# LCD.net
KiCad netlist of a schematic drawn in Altium Designer
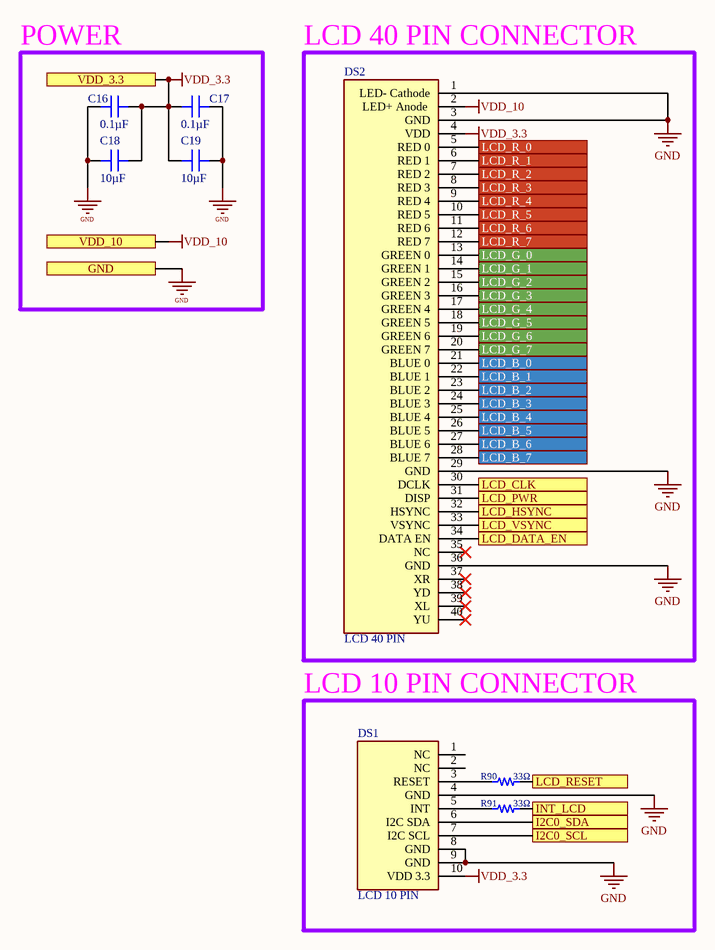
[diagram p0: LCD.SchDoc]

(export (version "E")
  (design (tool "Eeschema 10.0.6"))
  (components
    (comp (ref "C16")
      (value "0.1µF")
      (footprint "CAP 0603_1608 RF")
      (description "CAP CER 0.1UF 16V X7R 0603")
      (fields (field (name "MANUFACTURER") "KEMET") (field (name "VOLTAGE") "16V"))
      (libsource (lib "MVVVMAltiumDatabase") (part "Capacitor"))
    )
    (comp (ref "C17")
      (value "0.1µF")
      (footprint "CAP 0603_1608 RF")
      (description "CAP CER 0.1UF 16V X7R 0603")
      (fields (field (name "MANUFACTURER") "KEMET") (field (name "VOLTAGE") "16V"))
      (libsource (lib "MVVVMAltiumDatabase") (part "Capacitor"))
    )
    (comp (ref "C18")
      (value "10µF")
      (footprint "CAP 0603_1608")
      (description "CAP CER 010UF 25V X7R 0603")
      (fields (field (name "MANUFACTURER") "KEMET") (field (name "VOLTAGE") "25V"))
      (libsource (lib "MVVVMAltiumDatabase") (part "Capacitor"))
    )
    (comp (ref "C19")
      (value "10µF")
      (footprint "CAP 0603_1608")
      (description "CAP CER 010UF 25V X7R 0603")
      (fields (field (name "MANUFACTURER") "KEMET") (field (name "VOLTAGE") "25V"))
      (libsource (lib "MVVVMAltiumDatabase") (part "Capacitor"))
    )
    (comp (ref "DS1")
      (value "LCD 10 PIN")
      (footprint "4DLCD-70800480-CTP-CLB 10 PIN")
      (description "LED GRN/RED CLEAR 4SMD BOTTOM")
      (fields (field (name "MANUFACTURER") "Würth Elektronik"))
      (libsource (lib "MVVVMAltiumDatabase") (part "4DLCD-70800480-CTP-CLB 10 PIN"))
    )
    (comp (ref "DS2")
      (value "LCD 40 PIN")
      (footprint "4DLCD-70800480-CTP-CLB 40 PIN")
      (description "LED GRN/RED CLEAR 4SMD BOTTOM")
      (fields (field (name "MANUFACTURER") "Würth Elektronik"))
      (libsource (lib "MVVVMAltiumDatabase") (part "4DLCD-70800480-CTP-CLB 40 PIN"))
    )
    (comp (ref "R90")
      (value "33Ω")
      (footprint "RES 0201_0603")
      (description "RES SMD 33 OHM 1% 1/20W 0201")
      (fields (field (name "MANUFACTURER") "Vishay Dale") (field (name "TOLERANCE") "±1%"))
      (libsource (lib "MVVVMAltiumDatabase") (part "Resistor"))
    )
    (comp (ref "R91")
      (value "33Ω")
      (footprint "RES 0201_0603")
      (description "RES SMD 33 OHM 1% 1/20W 0201")
      (fields (field (name "MANUFACTURER") "Vishay Dale") (field (name "TOLERANCE") "±1%"))
      (libsource (lib "MVVVMAltiumDatabase") (part "Resistor"))
    )
  )
  (nets
    (net (code "1") (name "/I2C0_SCL") (class "Default")
      (node (ref "DS1") (pin "7") (pinfunction "I2C_SCL_7") (pintype "passive"))
    )
    (net (code "2") (name "/I2C0_SDA") (class "Default")
      (node (ref "DS1") (pin "6") (pinfunction "I2C_SDA_6") (pintype "passive"))
    )
    (net (code "3") (name "/INT_LCD") (class "Default")
      (node (ref "R91") (pin "2") (pinfunction "2_2") (pintype "passive"))
    )
    (net (code "4") (name "/LCD_B_0") (class "Default")
      (node (ref "DS2") (pin "21") (pinfunction "BLUE_0_21") (pintype "passive"))
    )
    (net (code "5") (name "/LCD_B_1") (class "Default")
      (node (ref "DS2") (pin "22") (pinfunction "BLUE_1_22") (pintype "passive"))
    )
    (net (code "6") (name "/LCD_B_2") (class "Default")
      (node (ref "DS2") (pin "23") (pinfunction "BLUE_2_23") (pintype "passive"))
    )
    (net (code "7") (name "/LCD_B_3") (class "Default")
      (node (ref "DS2") (pin "24") (pinfunction "BLUE_3_24") (pintype "passive"))
    )
    (net (code "8") (name "/LCD_B_4") (class "Default")
      (node (ref "DS2") (pin "25") (pinfunction "BLUE_4_25") (pintype "passive"))
    )
    (net (code "9") (name "/LCD_B_5") (class "Default")
      (node (ref "DS2") (pin "26") (pinfunction "BLUE_5_26") (pintype "passive"))
    )
    (net (code "10") (name "/LCD_B_6") (class "Default")
      (node (ref "DS2") (pin "27") (pinfunction "BLUE_6_27") (pintype "passive"))
    )
    (net (code "11") (name "/LCD_B_7") (class "Default")
      (node (ref "DS2") (pin "28") (pinfunction "BLUE_7_28") (pintype "passive"))
    )
    (net (code "12") (name "/LCD_CLK") (class "Default")
      (node (ref "DS2") (pin "30") (pinfunction "DCLK_30") (pintype "passive"))
    )
    (net (code "13") (name "/LCD_DATA_EN") (class "Default")
      (node (ref "DS2") (pin "34") (pinfunction "DATA_EN_34") (pintype "passive"))
    )
    (net (code "14") (name "/LCD_G_0") (class "Default")
      (node (ref "DS2") (pin "13") (pinfunction "GREEN_0_13") (pintype "passive"))
    )
    (net (code "15") (name "/LCD_G_1") (class "Default")
      (node (ref "DS2") (pin "14") (pinfunction "GREEN_1_14") (pintype "passive"))
    )
    (net (code "16") (name "/LCD_G_2") (class "Default")
      (node (ref "DS2") (pin "15") (pinfunction "GREEN_2_15") (pintype "passive"))
    )
    (net (code "17") (name "/LCD_G_3") (class "Default")
      (node (ref "DS2") (pin "16") (pinfunction "GREEN_3_16") (pintype "passive"))
    )
    (net (code "18") (name "/LCD_G_4") (class "Default")
      (node (ref "DS2") (pin "17") (pinfunction "GREEN_4_17") (pintype "passive"))
    )
    (net (code "19") (name "/LCD_G_5") (class "Default")
      (node (ref "DS2") (pin "18") (pinfunction "GREEN_5_18") (pintype "passive"))
    )
    (net (code "20") (name "/LCD_G_6") (class "Default")
      (node (ref "DS2") (pin "19") (pinfunction "GREEN_6_19") (pintype "passive"))
    )
    (net (code "21") (name "/LCD_G_7") (class "Default")
      (node (ref "DS2") (pin "20") (pinfunction "GREEN_7_20") (pintype "passive"))
    )
    (net (code "22") (name "/LCD_HSYNC") (class "Default")
      (node (ref "DS2") (pin "32") (pinfunction "HSYNC_32") (pintype "passive"))
    )
    (net (code "23") (name "/LCD_PWR") (class "Default")
      (node (ref "DS2") (pin "31") (pinfunction "DISP_31") (pintype "passive"))
    )
    (net (code "24") (name "/LCD_RESET") (class "Default")
      (node (ref "R90") (pin "2") (pinfunction "2_2") (pintype "passive"))
    )
    (net (code "25") (name "/LCD_R_0") (class "Default")
      (node (ref "DS2") (pin "5") (pinfunction "RED_0_5") (pintype "passive"))
    )
    (net (code "26") (name "/LCD_R_1") (class "Default")
      (node (ref "DS2") (pin "6") (pinfunction "RED_1_6") (pintype "passive"))
    )
    (net (code "27") (name "/LCD_R_2") (class "Default")
      (node (ref "DS2") (pin "7") (pinfunction "RED_2_7") (pintype "passive"))
    )
    (net (code "28") (name "/LCD_R_3") (class "Default")
      (node (ref "DS2") (pin "8") (pinfunction "RED_3_8") (pintype "passive"))
    )
    (net (code "29") (name "/LCD_R_4") (class "Default")
      (node (ref "DS2") (pin "9") (pinfunction "RED_4_9") (pintype "passive"))
    )
    (net (code "30") (name "/LCD_R_5") (class "Default")
      (node (ref "DS2") (pin "10") (pinfunction "RED_5_10") (pintype "passive"))
    )
    (net (code "31") (name "/LCD_R_6") (class "Default")
      (node (ref "DS2") (pin "11") (pinfunction "RED_6_11") (pintype "passive"))
    )
    (net (code "32") (name "/LCD_R_7") (class "Default")
      (node (ref "DS2") (pin "12") (pinfunction "RED_7_12") (pintype "passive"))
    )
    (net (code "33") (name "/LCD_VSYNC") (class "Default")
      (node (ref "DS2") (pin "33") (pinfunction "VSYNC_33") (pintype "passive"))
    )
    (net (code "34") (name "GND") (class "Default")
      (node (ref "C16") (pin "2") (pinfunction "2_2") (pintype "passive"))
      (node (ref "C17") (pin "1") (pinfunction "1_1") (pintype "passive"))
      (node (ref "C18") (pin "2") (pinfunction "2_2") (pintype "passive"))
      (node (ref "C19") (pin "1") (pinfunction "1_1") (pintype "passive"))
      (node (ref "DS1") (pin "4") (pinfunction "GND_4") (pintype "passive"))
      (node (ref "DS1") (pin "8") (pinfunction "GND_8") (pintype "passive"))
      (node (ref "DS1") (pin "9") (pinfunction "GND_9") (pintype "passive"))
      (node (ref "DS2") (pin "1") (pinfunction "LED-_Cathode_1") (pintype "passive"))
      (node (ref "DS2") (pin "29") (pinfunction "GND_29") (pintype "passive"))
      (node (ref "DS2") (pin "3") (pinfunction "GND_3") (pintype "passive"))
      (node (ref "DS2") (pin "36") (pinfunction "GND_36") (pintype "passive"))
    )
    (net (code "35") (name "Net-(DS1-INT)") (class "Default")
      (node (ref "DS1") (pin "5") (pinfunction "INT_5") (pintype "passive"))
      (node (ref "R91") (pin "1") (pinfunction "1_1") (pintype "passive"))
    )
    (net (code "36") (name "Net-(DS1-RESET)") (class "Default")
      (node (ref "DS1") (pin "3") (pinfunction "RESET_3") (pintype "passive"))
      (node (ref "R90") (pin "1") (pinfunction "1_1") (pintype "passive"))
    )
    (net (code "37") (name "VDD_3.3") (class "Default")
      (node (ref "C16") (pin "1") (pinfunction "1_1") (pintype "passive"))
      (node (ref "C17") (pin "2") (pinfunction "2_2") (pintype "passive"))
      (node (ref "C18") (pin "1") (pinfunction "1_1") (pintype "passive"))
      (node (ref "C19") (pin "2") (pinfunction "2_2") (pintype "passive"))
      (node (ref "DS1") (pin "10") (pinfunction "VDD_3.3_10") (pintype "passive"))
      (node (ref "DS2") (pin "4") (pinfunction "VDD_4") (pintype "passive"))
    )
    (net (code "38") (name "VDD_10") (class "Default")
      (node (ref "DS2") (pin "2") (pinfunction "LED+_Anode_2") (pintype "passive"))
    )
    (net (code "39") (name "unconnected-(DS1-NC-Pad1)") (class "Default")
      (node (ref "DS1") (pin "1") (pinfunction "NC_1") (pintype "passive"))
    )
    (net (code "40") (name "unconnected-(DS1-NC-Pad2)") (class "Default")
      (node (ref "DS1") (pin "2") (pinfunction "NC_2") (pintype "passive"))
    )
    (net (code "41") (name "unconnected-(DS2-NC-Pad35)") (class "Default")
      (node (ref "DS2") (pin "35") (pinfunction "NC_35") (pintype "passive+no_connect"))
    )
    (net (code "42") (name "unconnected-(DS2-XL-Pad39)") (class "Default")
      (node (ref "DS2") (pin "39") (pinfunction "XL_39") (pintype "passive+no_connect"))
    )
    (net (code "43") (name "unconnected-(DS2-XR-Pad37)") (class "Default")
      (node (ref "DS2") (pin "37") (pinfunction "XR_37") (pintype "passive+no_connect"))
    )
    (net (code "44") (name "unconnected-(DS2-YD-Pad38)") (class "Default")
      (node (ref "DS2") (pin "38") (pinfunction "YD_38") (pintype "passive+no_connect"))
    )
    (net (code "45") (name "unconnected-(DS2-YU-Pad40)") (class "Default")
      (node (ref "DS2") (pin "40") (pinfunction "YU_40") (pintype "passive+no_connect"))
    )
  )
)
